# Braking.net
KiCad netlist of a schematic drawn in Altium Designer
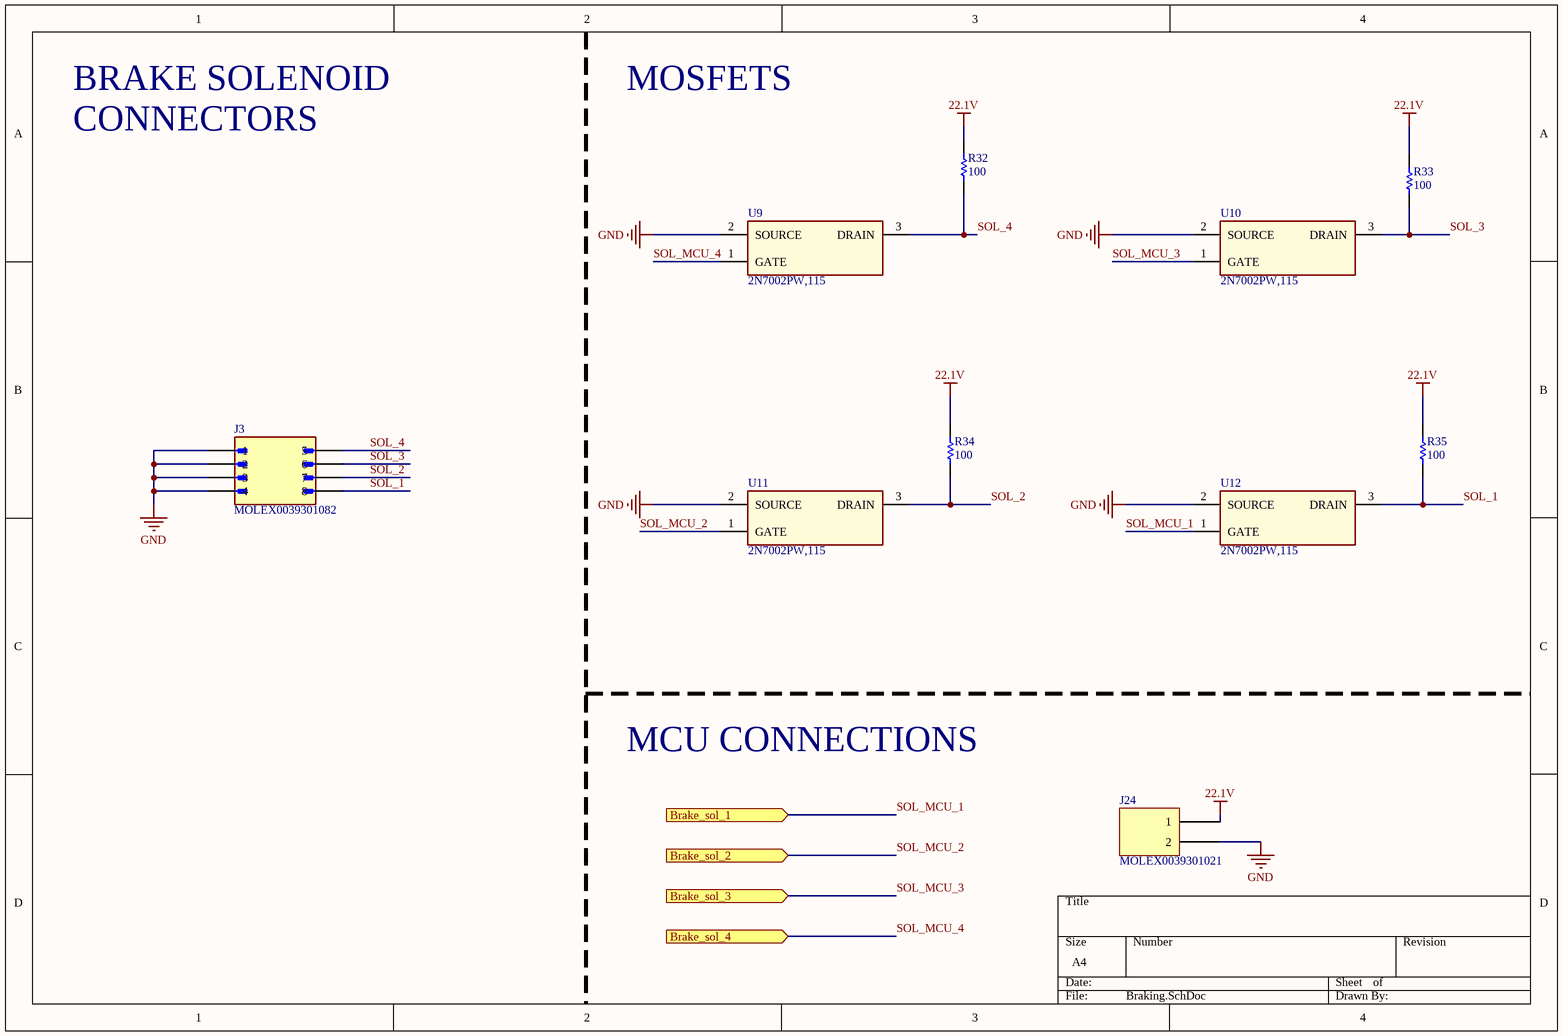
[diagram p0: Braking.SchDoc]

(export (version "E")
  (design (tool "Eeschema 10.0.6"))
  (components
    (comp (ref "J3")
      (value "MOLEX0039301082")
      (footprint "MOLEX0039301082")
      (description "Connector Header Through Hole, Right Angle 8 position 0.165\" (4.20mm)")
      (fields (field (name "MANUFACTURER") "Molex") (field (name "MANUFACTURER PART NUMBER") "0039301082"))
      (libsource (lib "GeneralConnectors") (part "MOLEX0039301082"))
    )
    (comp (ref "J24")
      (value "MOLEX0039301021")
      (footprint "MOLEX0039301021")
      (description "Connector Header Through Hole, Right Angle 2 pin 0.165\" (4.20mm)")
      (libsource (lib "GeneralConnectors") (part "MOLEX0039301021"))
    )
    (comp (ref "R32")
      (value "100")
      (footprint "0805 - Resistor")
      (description "Resistor")
      (libsource (lib "General") (part "Resistor"))
    )
    (comp (ref "R33")
      (value "100")
      (footprint "0805 - Resistor")
      (description "Resistor")
      (libsource (lib "General") (part "Resistor"))
    )
    (comp (ref "R34")
      (value "100")
      (footprint "0805 - Resistor")
      (description "Resistor")
      (libsource (lib "General") (part "Resistor"))
    )
    (comp (ref "R35")
      (value "100")
      (footprint "0805 - Resistor")
      (description "Resistor")
      (libsource (lib "General") (part "Resistor"))
    )
    (comp (ref "U9")
      (value "2N7002PW,115")
      (footprint "SOT65P210X110-3N")
      (description "N-Channel 60V 310mA (Ta) 260mW (Ta) Surface Mount SOT-323")
      (fields (field (name "DIGI-KEY_PART_NUMBER") "1727-4793-1-ND") (field (name "MF") "Nexperia USA"))
      (libsource (lib "Embedded") (part "2N7002PW,115"))
    )
    (comp (ref "U10")
      (value "2N7002PW,115")
      (footprint "SOT65P210X110-3N")
      (description "N-Channel 60V 310mA (Ta) 260mW (Ta) Surface Mount SOT-323")
      (fields (field (name "DIGI-KEY_PART_NUMBER") "1727-4793-1-ND") (field (name "MF") "Nexperia USA"))
      (libsource (lib "Embedded") (part "2N7002PW,115"))
    )
    (comp (ref "U11")
      (value "2N7002PW,115")
      (footprint "SOT65P210X110-3N")
      (description "N-Channel 60V 310mA (Ta) 260mW (Ta) Surface Mount SOT-323")
      (fields (field (name "DIGI-KEY_PART_NUMBER") "1727-4793-1-ND") (field (name "MF") "Nexperia USA"))
      (libsource (lib "Embedded") (part "2N7002PW,115"))
    )
    (comp (ref "U12")
      (value "2N7002PW,115")
      (footprint "SOT65P210X110-3N")
      (description "N-Channel 60V 310mA (Ta) 260mW (Ta) Surface Mount SOT-323")
      (fields (field (name "DIGI-KEY_PART_NUMBER") "1727-4793-1-ND") (field (name "MF") "Nexperia USA"))
      (libsource (lib "Embedded") (part "2N7002PW,115"))
    )
  )
  (nets
    (net (code "1") (name "/SOL_1") (class "Default")
      (node (ref "J3") (pin "8") (pinfunction "8_8") (pintype "passive"))
      (node (ref "R35") (pin "1") (pinfunction "1_1") (pintype "passive"))
      (node (ref "U12") (pin "3") (pinfunction "DRAIN_3") (pintype "passive"))
    )
    (net (code "2") (name "/SOL_2") (class "Default")
      (node (ref "J3") (pin "7") (pinfunction "7_7") (pintype "passive"))
      (node (ref "R34") (pin "1") (pinfunction "1_1") (pintype "passive"))
      (node (ref "U11") (pin "3") (pinfunction "DRAIN_3") (pintype "passive"))
    )
    (net (code "3") (name "/SOL_3") (class "Default")
      (node (ref "J3") (pin "6") (pinfunction "6_6") (pintype "passive"))
      (node (ref "R33") (pin "1") (pinfunction "1_1") (pintype "passive"))
      (node (ref "U10") (pin "3") (pinfunction "DRAIN_3") (pintype "passive"))
    )
    (net (code "4") (name "/SOL_4") (class "Default")
      (node (ref "J3") (pin "5") (pinfunction "5_5") (pintype "passive"))
      (node (ref "R32") (pin "1") (pinfunction "1_1") (pintype "passive"))
      (node (ref "U9") (pin "3") (pinfunction "DRAIN_3") (pintype "passive"))
    )
    (net (code "5") (name "/SOL_MCU_1") (class "Default")
      (node (ref "U12") (pin "1") (pinfunction "GATE_1") (pintype "passive"))
    )
    (net (code "6") (name "/SOL_MCU_2") (class "Default")
      (node (ref "U11") (pin "1") (pinfunction "GATE_1") (pintype "passive"))
    )
    (net (code "7") (name "/SOL_MCU_3") (class "Default")
      (node (ref "U10") (pin "1") (pinfunction "GATE_1") (pintype "passive"))
    )
    (net (code "8") (name "/SOL_MCU_4") (class "Default")
      (node (ref "U9") (pin "1") (pinfunction "GATE_1") (pintype "passive"))
    )
    (net (code "9") (name "22.1V") (class "Default")
      (node (ref "J24") (pin "1") (pinfunction "1_1") (pintype "passive"))
      (node (ref "R32") (pin "2") (pinfunction "2_2") (pintype "passive"))
      (node (ref "R33") (pin "2") (pinfunction "2_2") (pintype "passive"))
      (node (ref "R34") (pin "2") (pinfunction "2_2") (pintype "passive"))
      (node (ref "R35") (pin "2") (pinfunction "2_2") (pintype "passive"))
    )
    (net (code "10") (name "GND") (class "Default")
      (node (ref "J24") (pin "2") (pinfunction "2_2") (pintype "passive"))
      (node (ref "J3") (pin "1") (pinfunction "1_1") (pintype "passive"))
      (node (ref "J3") (pin "2") (pinfunction "2_2") (pintype "passive"))
      (node (ref "J3") (pin "3") (pinfunction "3_3") (pintype "passive"))
      (node (ref "J3") (pin "4") (pinfunction "4_4") (pintype "passive"))
      (node (ref "U10") (pin "2") (pinfunction "SOURCE_2") (pintype "passive"))
      (node (ref "U11") (pin "2") (pinfunction "SOURCE_2") (pintype "passive"))
      (node (ref "U12") (pin "2") (pinfunction "SOURCE_2") (pintype "passive"))
      (node (ref "U9") (pin "2") (pinfunction "SOURCE_2") (pintype "passive"))
    )
  )
)
